# Prosthesis_Sensor_Shield.net
KiCad netlist of a schematic drawn in EAGLE
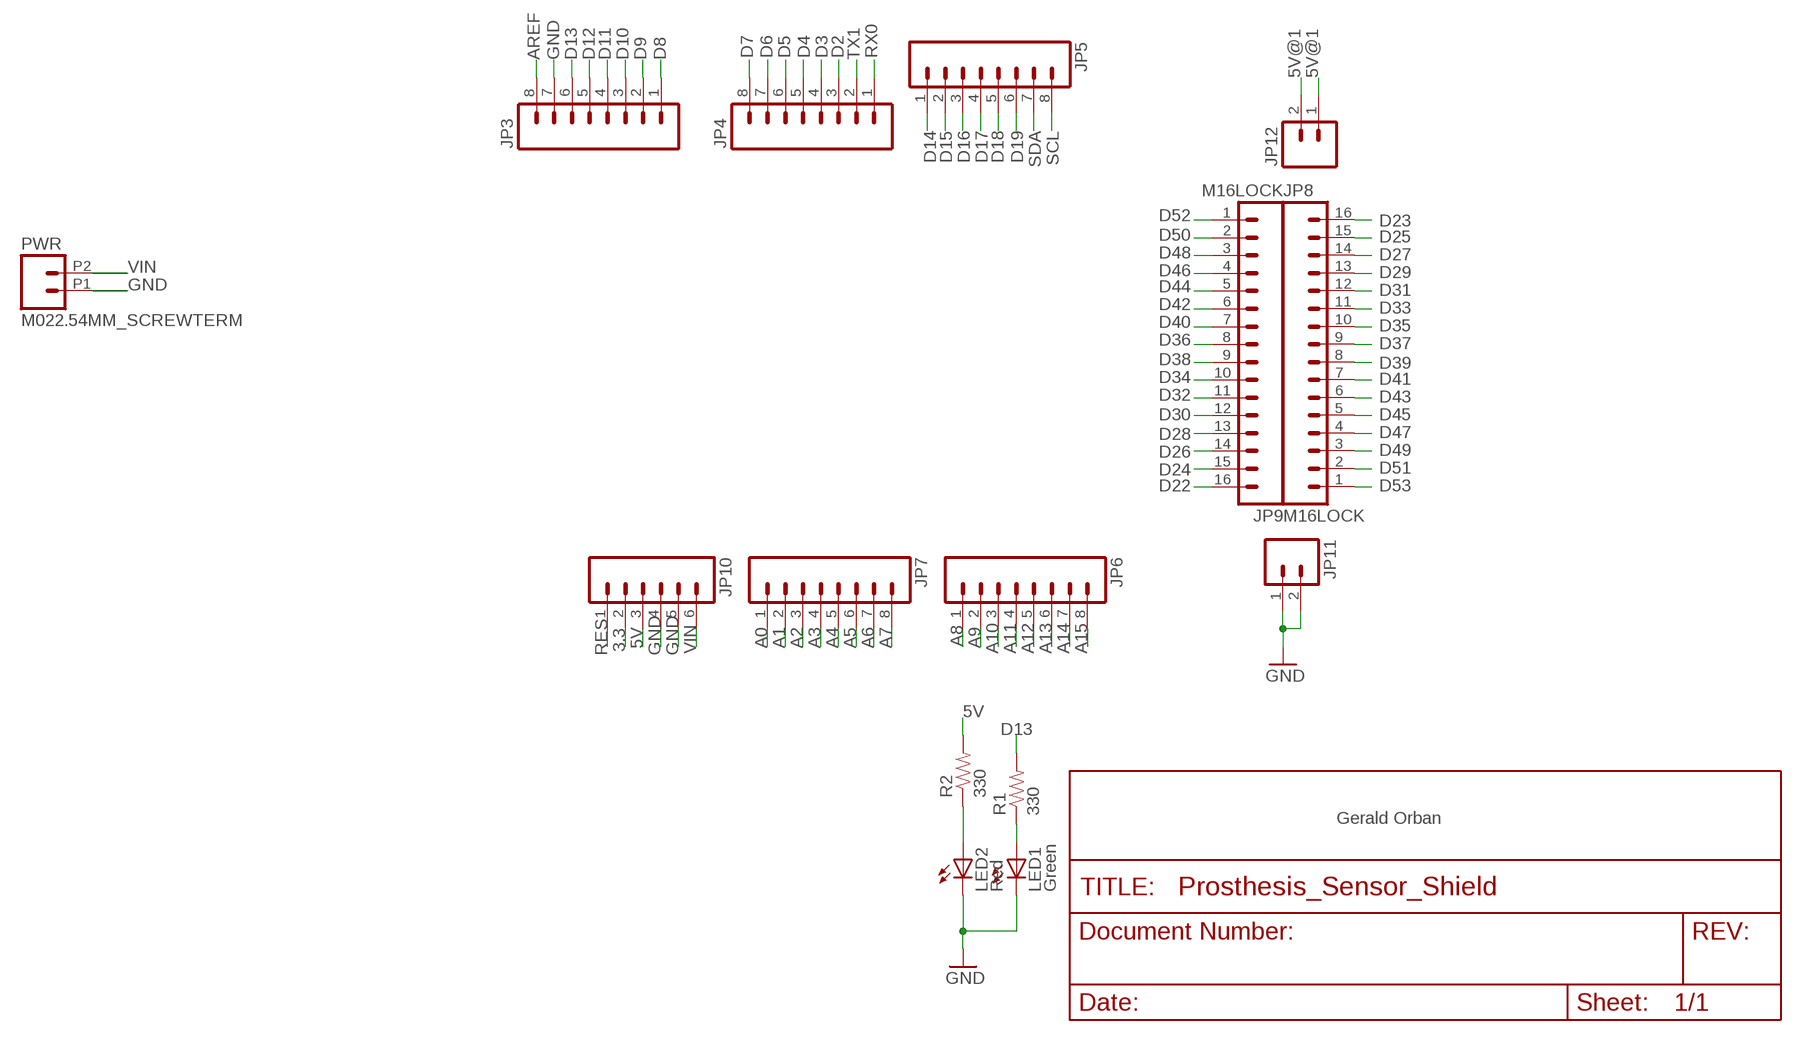
[diagram p0: schematic, sheet 1]

(export (version "E")
  (design (tool "Eeschema 10.0.6"))
  (components
    (comp (ref "JP3")
      (value "M08LOCK")
      (footprint "eagle-import:1X08_LOCK")
      (libsource (lib "eagle-import") (part "M08LOCK"))
    )
    (comp (ref "JP4")
      (value "M08LOCK")
      (footprint "eagle-import:1X08_LOCK")
      (libsource (lib "eagle-import") (part "M08LOCK"))
    )
    (comp (ref "JP5")
      (value "M08LOCK")
      (footprint "eagle-import:1X08_LOCK")
      (libsource (lib "eagle-import") (part "M08LOCK"))
    )
    (comp (ref "JP6")
      (value "M08LOCK")
      (footprint "eagle-import:1X08_LOCK")
      (libsource (lib "eagle-import") (part "M08LOCK"))
    )
    (comp (ref "JP7")
      (value "M08LOCK")
      (footprint "eagle-import:1X08_LOCK")
      (libsource (lib "eagle-import") (part "M08LOCK"))
    )
    (comp (ref "JP8")
      (value "M16LOCK")
      (footprint "eagle-import:1X16_LOCK")
      (libsource (lib "eagle-import") (part "M16LOCK"))
    )
    (comp (ref "JP9")
      (value "M16LOCK")
      (footprint "eagle-import:1X16_LOCK")
      (libsource (lib "eagle-import") (part "M16LOCK"))
    )
    (comp (ref "JP10")
      (value "M06LOCK")
      (footprint "eagle-import:1X06_LOCK")
      (libsource (lib "eagle-import") (part "M06LOCK"))
    )
    (comp (ref "JP11")
      (value "M02LOCK")
      (footprint "eagle-import:1X02_LOCK")
      (libsource (lib "eagle-import") (part "M02LOCK"))
    )
    (comp (ref "JP12")
      (value "M02LOCK")
      (footprint "eagle-import:1X02_LOCK")
      (libsource (lib "eagle-import") (part "M02LOCK"))
    )
    (comp (ref "LED1")
      (value "Green")
      (footprint "eagle-import:LED-1206")
      (libsource (lib "eagle-import") (part "LED1206"))
    )
    (comp (ref "LED2")
      (value "Red")
      (footprint "eagle-import:LED-1206")
      (libsource (lib "eagle-import") (part "LED1206"))
    )
    (comp (ref "PWR")
      (value "M022.54MM_SCREWTERM")
      (footprint "eagle-import:1X02_2.54_SCREWTERM")
      (libsource (lib "eagle-import") (part "M022.54MM_SCREWTERM"))
    )
    (comp (ref "R1")
      (value "330")
      (footprint "eagle-import:0603-RES")
      (libsource (lib "eagle-import") (part "RESISTOR0603-RES"))
    )
    (comp (ref "R2")
      (value "330")
      (footprint "eagle-import:0603-RES")
      (libsource (lib "eagle-import") (part "RESISTOR0603-RES"))
    )
  )
  (nets
    (net (code "1") (name "/3.3") (class "Default")
      (node (ref "JP10") (pin "2") (pinfunction "2_2") (pintype "passive"))
    )
    (net (code "2") (name "/5V") (class "Default")
      (node (ref "JP10") (pin "3") (pinfunction "3_3") (pintype "passive"))
      (node (ref "R2") (pin "2") (pinfunction "2_2") (pintype "passive"))
    )
    (net (code "3") (name "/5V@1") (class "Default")
      (node (ref "JP12") (pin "1") (pinfunction "1_1") (pintype "passive"))
      (node (ref "JP12") (pin "2") (pinfunction "2_2") (pintype "passive"))
    )
    (net (code "4") (name "/A0") (class "Default")
      (node (ref "JP7") (pin "1") (pinfunction "1_1") (pintype "passive"))
    )
    (net (code "5") (name "/A1") (class "Default")
      (node (ref "JP7") (pin "2") (pinfunction "2_2") (pintype "passive"))
    )
    (net (code "6") (name "/A2") (class "Default")
      (node (ref "JP7") (pin "3") (pinfunction "3_3") (pintype "passive"))
    )
    (net (code "7") (name "/A3") (class "Default")
      (node (ref "JP7") (pin "4") (pinfunction "4_4") (pintype "passive"))
    )
    (net (code "8") (name "/A4") (class "Default")
      (node (ref "JP7") (pin "5") (pinfunction "5_5") (pintype "passive"))
    )
    (net (code "9") (name "/A5") (class "Default")
      (node (ref "JP7") (pin "6") (pinfunction "6_6") (pintype "passive"))
    )
    (net (code "10") (name "/A6") (class "Default")
      (node (ref "JP7") (pin "7") (pinfunction "7_7") (pintype "passive"))
    )
    (net (code "11") (name "/A7") (class "Default")
      (node (ref "JP7") (pin "8") (pinfunction "8_8") (pintype "passive"))
    )
    (net (code "12") (name "/A8") (class "Default")
      (node (ref "JP6") (pin "1") (pinfunction "1_1") (pintype "passive"))
    )
    (net (code "13") (name "/A9") (class "Default")
      (node (ref "JP6") (pin "2") (pinfunction "2_2") (pintype "passive"))
    )
    (net (code "14") (name "/A10") (class "Default")
      (node (ref "JP6") (pin "3") (pinfunction "3_3") (pintype "passive"))
    )
    (net (code "15") (name "/A11") (class "Default")
      (node (ref "JP6") (pin "4") (pinfunction "4_4") (pintype "passive"))
    )
    (net (code "16") (name "/A12") (class "Default")
      (node (ref "JP6") (pin "5") (pinfunction "5_5") (pintype "passive"))
    )
    (net (code "17") (name "/A13") (class "Default")
      (node (ref "JP6") (pin "6") (pinfunction "6_6") (pintype "passive"))
    )
    (net (code "18") (name "/A14") (class "Default")
      (node (ref "JP6") (pin "7") (pinfunction "7_7") (pintype "passive"))
    )
    (net (code "19") (name "/A15") (class "Default")
      (node (ref "JP6") (pin "8") (pinfunction "8_8") (pintype "passive"))
    )
    (net (code "20") (name "/AREF") (class "Default")
      (node (ref "JP3") (pin "8") (pinfunction "8_8") (pintype "passive"))
    )
    (net (code "21") (name "/D2") (class "Default")
      (node (ref "JP4") (pin "3") (pinfunction "3_3") (pintype "passive"))
    )
    (net (code "22") (name "/D3") (class "Default")
      (node (ref "JP4") (pin "4") (pinfunction "4_4") (pintype "passive"))
    )
    (net (code "23") (name "/D4") (class "Default")
      (node (ref "JP4") (pin "5") (pinfunction "5_5") (pintype "passive"))
    )
    (net (code "24") (name "/D5") (class "Default")
      (node (ref "JP4") (pin "6") (pinfunction "6_6") (pintype "passive"))
    )
    (net (code "25") (name "/D6") (class "Default")
      (node (ref "JP4") (pin "7") (pinfunction "7_7") (pintype "passive"))
    )
    (net (code "26") (name "/D7") (class "Default")
      (node (ref "JP4") (pin "8") (pinfunction "8_8") (pintype "passive"))
    )
    (net (code "27") (name "/D8") (class "Default")
      (node (ref "JP3") (pin "1") (pinfunction "1_1") (pintype "passive"))
    )
    (net (code "28") (name "/D9") (class "Default")
      (node (ref "JP3") (pin "2") (pinfunction "2_2") (pintype "passive"))
    )
    (net (code "29") (name "/D10") (class "Default")
      (node (ref "JP3") (pin "3") (pinfunction "3_3") (pintype "passive"))
    )
    (net (code "30") (name "/D11") (class "Default")
      (node (ref "JP3") (pin "4") (pinfunction "4_4") (pintype "passive"))
    )
    (net (code "31") (name "/D12") (class "Default")
      (node (ref "JP3") (pin "5") (pinfunction "5_5") (pintype "passive"))
    )
    (net (code "32") (name "/D13") (class "Default")
      (node (ref "JP3") (pin "6") (pinfunction "6_6") (pintype "passive"))
      (node (ref "R1") (pin "2") (pinfunction "2_2") (pintype "passive"))
    )
    (net (code "33") (name "/D14") (class "Default")
      (node (ref "JP5") (pin "1") (pinfunction "1_1") (pintype "passive"))
    )
    (net (code "34") (name "/D15") (class "Default")
      (node (ref "JP5") (pin "2") (pinfunction "2_2") (pintype "passive"))
    )
    (net (code "35") (name "/D16") (class "Default")
      (node (ref "JP5") (pin "3") (pinfunction "3_3") (pintype "passive"))
    )
    (net (code "36") (name "/D17") (class "Default")
      (node (ref "JP5") (pin "4") (pinfunction "4_4") (pintype "passive"))
    )
    (net (code "37") (name "/D18") (class "Default")
      (node (ref "JP5") (pin "5") (pinfunction "5_5") (pintype "passive"))
    )
    (net (code "38") (name "/D19") (class "Default")
      (node (ref "JP5") (pin "6") (pinfunction "6_6") (pintype "passive"))
    )
    (net (code "39") (name "/D22") (class "Default")
      (node (ref "JP9") (pin "16") (pinfunction "16_16") (pintype "passive"))
    )
    (net (code "40") (name "/D23") (class "Default")
      (node (ref "JP8") (pin "16") (pinfunction "16_16") (pintype "passive"))
    )
    (net (code "41") (name "/D24") (class "Default")
      (node (ref "JP9") (pin "15") (pinfunction "15_15") (pintype "passive"))
    )
    (net (code "42") (name "/D25") (class "Default")
      (node (ref "JP8") (pin "15") (pinfunction "15_15") (pintype "passive"))
    )
    (net (code "43") (name "/D26") (class "Default")
      (node (ref "JP9") (pin "14") (pinfunction "14_14") (pintype "passive"))
    )
    (net (code "44") (name "/D27") (class "Default")
      (node (ref "JP8") (pin "14") (pinfunction "14_14") (pintype "passive"))
    )
    (net (code "45") (name "/D28") (class "Default")
      (node (ref "JP9") (pin "13") (pinfunction "13_13") (pintype "passive"))
    )
    (net (code "46") (name "/D29") (class "Default")
      (node (ref "JP8") (pin "13") (pinfunction "13_13") (pintype "passive"))
    )
    (net (code "47") (name "/D30") (class "Default")
      (node (ref "JP9") (pin "12") (pinfunction "12_12") (pintype "passive"))
    )
    (net (code "48") (name "/D31") (class "Default")
      (node (ref "JP8") (pin "12") (pinfunction "12_12") (pintype "passive"))
    )
    (net (code "49") (name "/D32") (class "Default")
      (node (ref "JP9") (pin "11") (pinfunction "11_11") (pintype "passive"))
    )
    (net (code "50") (name "/D33") (class "Default")
      (node (ref "JP8") (pin "11") (pinfunction "11_11") (pintype "passive"))
    )
    (net (code "51") (name "/D34") (class "Default")
      (node (ref "JP9") (pin "10") (pinfunction "10_10") (pintype "passive"))
    )
    (net (code "52") (name "/D35") (class "Default")
      (node (ref "JP8") (pin "10") (pinfunction "10_10") (pintype "passive"))
    )
    (net (code "53") (name "/D36") (class "Default")
      (node (ref "JP9") (pin "9") (pinfunction "9_9") (pintype "passive"))
    )
    (net (code "54") (name "/D37") (class "Default")
      (node (ref "JP8") (pin "9") (pinfunction "9_9") (pintype "passive"))
    )
    (net (code "55") (name "/D38") (class "Default")
      (node (ref "JP9") (pin "8") (pinfunction "8_8") (pintype "passive"))
    )
    (net (code "56") (name "/D39") (class "Default")
      (node (ref "JP8") (pin "8") (pinfunction "8_8") (pintype "passive"))
    )
    (net (code "57") (name "/D40") (class "Default")
      (node (ref "JP9") (pin "7") (pinfunction "7_7") (pintype "passive"))
    )
    (net (code "58") (name "/D41") (class "Default")
      (node (ref "JP8") (pin "7") (pinfunction "7_7") (pintype "passive"))
    )
    (net (code "59") (name "/D42") (class "Default")
      (node (ref "JP9") (pin "6") (pinfunction "6_6") (pintype "passive"))
    )
    (net (code "60") (name "/D43") (class "Default")
      (node (ref "JP8") (pin "6") (pinfunction "6_6") (pintype "passive"))
    )
    (net (code "61") (name "/D44") (class "Default")
      (node (ref "JP9") (pin "5") (pinfunction "5_5") (pintype "passive"))
    )
    (net (code "62") (name "/D45") (class "Default")
      (node (ref "JP8") (pin "5") (pinfunction "5_5") (pintype "passive"))
    )
    (net (code "63") (name "/D46") (class "Default")
      (node (ref "JP9") (pin "4") (pinfunction "4_4") (pintype "passive"))
    )
    (net (code "64") (name "/D47") (class "Default")
      (node (ref "JP8") (pin "4") (pinfunction "4_4") (pintype "passive"))
    )
    (net (code "65") (name "/D48") (class "Default")
      (node (ref "JP9") (pin "3") (pinfunction "3_3") (pintype "passive"))
    )
    (net (code "66") (name "/D49") (class "Default")
      (node (ref "JP8") (pin "3") (pinfunction "3_3") (pintype "passive"))
    )
    (net (code "67") (name "/D50") (class "Default")
      (node (ref "JP9") (pin "2") (pinfunction "2_2") (pintype "passive"))
    )
    (net (code "68") (name "/D51") (class "Default")
      (node (ref "JP8") (pin "2") (pinfunction "2_2") (pintype "passive"))
    )
    (net (code "69") (name "/D52") (class "Default")
      (node (ref "JP9") (pin "1") (pinfunction "1_1") (pintype "passive"))
    )
    (net (code "70") (name "/D53") (class "Default")
      (node (ref "JP8") (pin "1") (pinfunction "1_1") (pintype "passive"))
    )
    (net (code "71") (name "/RES") (class "Default")
      (node (ref "JP10") (pin "1") (pinfunction "1_1") (pintype "passive"))
    )
    (net (code "72") (name "/RX0") (class "Default")
      (node (ref "JP4") (pin "1") (pinfunction "1_1") (pintype "passive"))
    )
    (net (code "73") (name "/SCL") (class "Default")
      (node (ref "JP5") (pin "8") (pinfunction "8_8") (pintype "passive"))
    )
    (net (code "74") (name "/SDA") (class "Default")
      (node (ref "JP5") (pin "7") (pinfunction "7_7") (pintype "passive"))
    )
    (net (code "75") (name "/TX1") (class "Default")
      (node (ref "JP4") (pin "2") (pinfunction "2_2") (pintype "passive"))
    )
    (net (code "76") (name "/VIN") (class "Default")
      (node (ref "JP10") (pin "6") (pinfunction "6_6") (pintype "passive"))
      (node (ref "PWR") (pin "P2") (pinfunction "2_P2") (pintype "passive"))
    )
    (net (code "77") (name "GND") (class "Default")
      (node (ref "JP10") (pin "4") (pinfunction "4_4") (pintype "passive"))
      (node (ref "JP10") (pin "5") (pinfunction "5_5") (pintype "passive"))
      (node (ref "JP11") (pin "1") (pinfunction "1_1") (pintype "passive"))
      (node (ref "JP11") (pin "2") (pinfunction "2_2") (pintype "passive"))
      (node (ref "JP3") (pin "7") (pinfunction "7_7") (pintype "passive"))
      (node (ref "LED1") (pin "C") (pinfunction "C_C") (pintype "passive"))
      (node (ref "LED2") (pin "C") (pinfunction "C_C") (pintype "passive"))
      (node (ref "PWR") (pin "P1") (pinfunction "1_P1") (pintype "passive"))
    )
    (net (code "78") (name "Net-(LED1-PadA)") (class "Default")
      (node (ref "LED1") (pin "A") (pinfunction "A_A") (pintype "passive"))
      (node (ref "R1") (pin "1") (pinfunction "1_1") (pintype "passive"))
    )
    (net (code "79") (name "Net-(LED2-PadA)") (class "Default")
      (node (ref "LED2") (pin "A") (pinfunction "A_A") (pintype "passive"))
      (node (ref "R2") (pin "1") (pinfunction "1_1") (pintype "passive"))
    )
  )
)
